# AKS.net
KiCad netlist of a schematic drawn in EAGLE
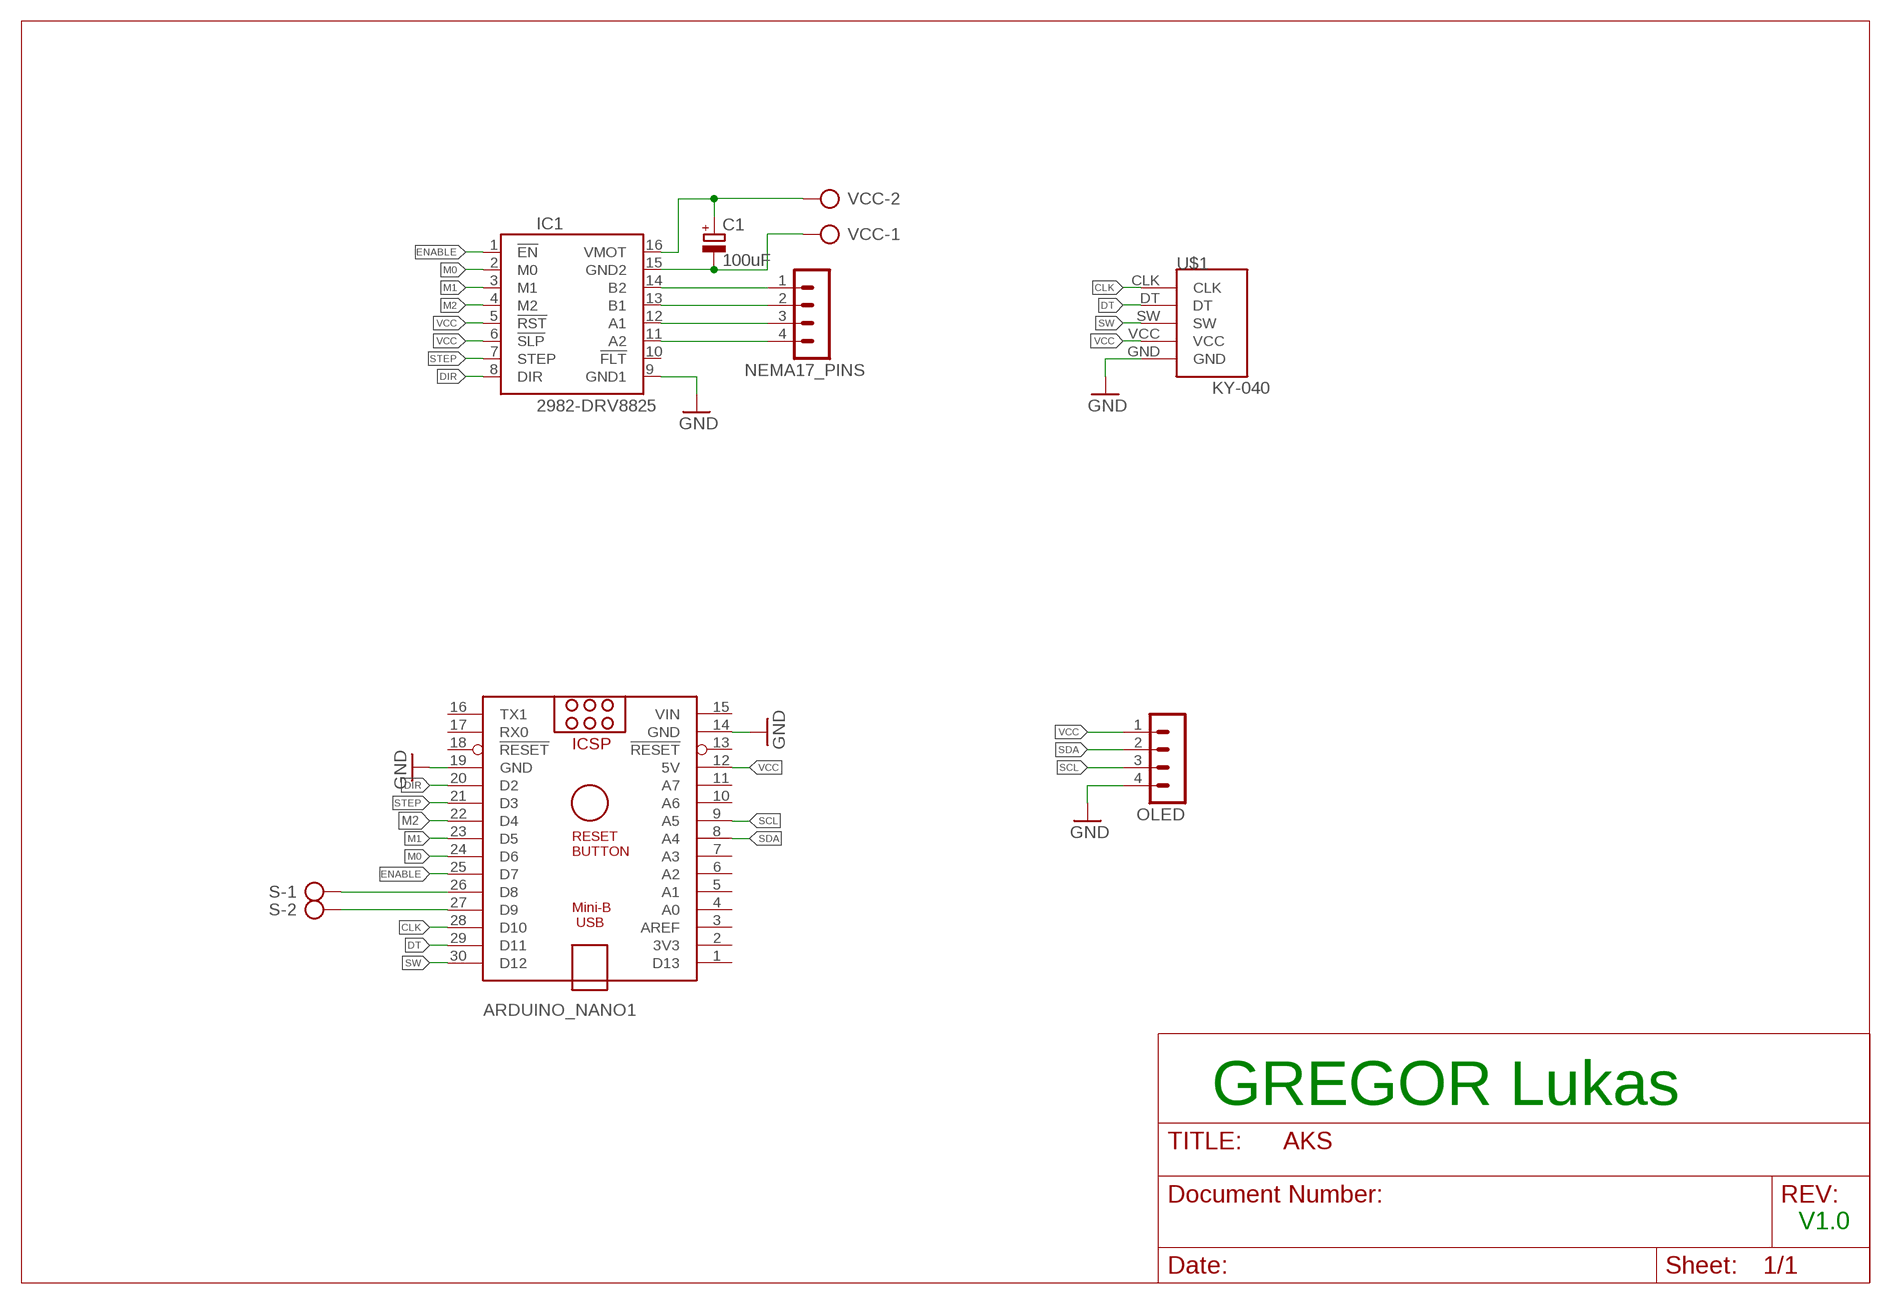
[diagram p0: schematic, sheet 1]

(export (version "E")
  (design (tool "Eeschema 10.0.6"))
  (components
    (comp (ref "ARDUINO_NANO1")
      (value "ARDUINO_NANO")
      (footprint "eagle-import:ARDUINO_NANO")
      (libsource (lib "eagle-import") (part "ARDUINO_NANO"))
    )
    (comp (ref "C1")
      (value "100uF")
      (footprint "eagle-import:E5-10,5")
      (libsource (lib "eagle-import") (part "CPOL-EUE5-10.5"))
    )
    (comp (ref "IC1")
      (value "2982-DRV8825")
      (footprint "eagle-import:DRV8825")
      (libsource (lib "eagle-import") (part "2982-DRV8825"))
    )
    (comp (ref "NEMA17_PINS")
      (value "MA04-1")
      (footprint "eagle-import:MA04-1")
      (libsource (lib "eagle-import") (part "MA04-1"))
    )
    (comp (ref "OLED")
      (value "MA04-1")
      (footprint "eagle-import:MA04-1")
      (libsource (lib "eagle-import") (part "MA04-1"))
    )
    (comp (ref "S")
      (value "AK500/2")
      (footprint "eagle-import:AK500_2")
      (libsource (lib "eagle-import") (part "AK500/2"))
    )
    (comp (ref "U$1")
      (value "KY-040")
      (footprint "eagle-import:KY-040-PORT")
      (fields (field (name "MF") "Joy-IT"))
      (libsource (lib "eagle-import") (part "KY-040"))
    )
    (comp (ref "VCC")
      (value "AK500/2")
      (footprint "eagle-import:AK500_2")
      (libsource (lib "eagle-import") (part "AK500/2"))
    )
  )
  (nets
    (net (code "1") (name "/VIN") (class "Default")
      (node (ref "ARDUINO_NANO1") (pin "15") (pinfunction "VIN_15") (pintype "power_in"))
    )
    (net (code "2") (name "CLK") (class "Default")
      (node (ref "ARDUINO_NANO1") (pin "28") (pinfunction "D10_28") (pintype "bidirectional"))
      (node (ref "U$1") (pin "CLK") (pinfunction "CLK_CLK") (pintype "output"))
    )
    (net (code "3") (name "DIR") (class "Default")
      (node (ref "ARDUINO_NANO1") (pin "20") (pinfunction "D2_20") (pintype "bidirectional"))
      (node (ref "IC1") (pin "8") (pinfunction "DIR_8") (pintype "input"))
    )
    (net (code "4") (name "DT") (class "Default")
      (node (ref "ARDUINO_NANO1") (pin "29") (pinfunction "D11_29") (pintype "bidirectional"))
      (node (ref "U$1") (pin "DT") (pinfunction "DT_DT") (pintype "output"))
    )
    (net (code "5") (name "ENABLE") (class "Default")
      (node (ref "ARDUINO_NANO1") (pin "25") (pinfunction "D7_25") (pintype "bidirectional"))
      (node (ref "IC1") (pin "1") (pinfunction "~{EN}_1") (pintype "passive"))
    )
    (net (code "6") (name "GND") (class "Default")
      (node (ref "ARDUINO_NANO1") (pin "14") (pinfunction "GND_14") (pintype "power_in"))
      (node (ref "ARDUINO_NANO1") (pin "19") (pinfunction "GND_19") (pintype "power_in"))
      (node (ref "IC1") (pin "9") (pinfunction "GND1_9") (pintype "power_in"))
      (node (ref "OLED") (pin "4") (pinfunction "4_4") (pintype "passive"))
      (node (ref "U$1") (pin "GND") (pinfunction "GND_GND") (pintype "power_in"))
    )
    (net (code "7") (name "M0") (class "Default")
      (node (ref "ARDUINO_NANO1") (pin "24") (pinfunction "D6_24") (pintype "bidirectional"))
      (node (ref "IC1") (pin "2") (pinfunction "M0_2") (pintype "passive"))
    )
    (net (code "8") (name "M1") (class "Default")
      (node (ref "ARDUINO_NANO1") (pin "23") (pinfunction "D5_23") (pintype "bidirectional"))
      (node (ref "IC1") (pin "3") (pinfunction "M1_3") (pintype "passive"))
    )
    (net (code "9") (name "M2") (class "Default")
      (node (ref "ARDUINO_NANO1") (pin "22") (pinfunction "D4_22") (pintype "bidirectional"))
      (node (ref "IC1") (pin "4") (pinfunction "M2_4") (pintype "passive"))
    )
    (net (code "10") (name "Net-(ARDUINO_NANO1-D8)") (class "Default")
      (node (ref "ARDUINO_NANO1") (pin "26") (pinfunction "D8_26") (pintype "bidirectional"))
      (node (ref "S") (pin "1") (pinfunction "KL_1") (pintype "passive"))
    )
    (net (code "11") (name "Net-(ARDUINO_NANO1-D9)") (class "Default")
      (node (ref "ARDUINO_NANO1") (pin "27") (pinfunction "D9_27") (pintype "bidirectional"))
      (node (ref "S") (pin "2") (pinfunction "KL_2") (pintype "passive"))
    )
    (net (code "12") (name "Net-(IC1-A1)") (class "Default")
      (node (ref "IC1") (pin "12") (pinfunction "A1_12") (pintype "output"))
      (node (ref "NEMA17_PINS") (pin "3") (pinfunction "3_3") (pintype "passive"))
    )
    (net (code "13") (name "Net-(IC1-A2)") (class "Default")
      (node (ref "IC1") (pin "11") (pinfunction "A2_11") (pintype "output"))
      (node (ref "NEMA17_PINS") (pin "4") (pinfunction "4_4") (pintype "passive"))
    )
    (net (code "14") (name "Net-(IC1-B1)") (class "Default")
      (node (ref "IC1") (pin "13") (pinfunction "B1_13") (pintype "output"))
      (node (ref "NEMA17_PINS") (pin "2") (pinfunction "2_2") (pintype "passive"))
    )
    (net (code "15") (name "Net-(IC1-B2)") (class "Default")
      (node (ref "IC1") (pin "14") (pinfunction "B2_14") (pintype "output"))
      (node (ref "NEMA17_PINS") (pin "1") (pinfunction "1_1") (pintype "passive"))
    )
    (net (code "16") (name "Net-(IC1-GND2)") (class "Default")
      (node (ref "C1") (pin "-") (pinfunction "-_-") (pintype "passive"))
      (node (ref "IC1") (pin "15") (pinfunction "GND2_15") (pintype "power_in"))
      (node (ref "VCC") (pin "1") (pinfunction "KL_1") (pintype "passive"))
    )
    (net (code "17") (name "Net-(IC1-VMOT)") (class "Default")
      (node (ref "C1") (pin "+") (pinfunction "+_+") (pintype "passive"))
      (node (ref "IC1") (pin "16") (pinfunction "VMOT_16") (pintype "power_in"))
      (node (ref "VCC") (pin "2") (pinfunction "KL_2") (pintype "passive"))
    )
    (net (code "18") (name "SCL") (class "Default")
      (node (ref "ARDUINO_NANO1") (pin "9") (pinfunction "A5_9") (pintype "bidirectional"))
      (node (ref "OLED") (pin "3") (pinfunction "3_3") (pintype "passive"))
    )
    (net (code "19") (name "SDA") (class "Default")
      (node (ref "ARDUINO_NANO1") (pin "8") (pinfunction "A4_8") (pintype "bidirectional"))
      (node (ref "OLED") (pin "2") (pinfunction "2_2") (pintype "passive"))
    )
    (net (code "20") (name "STEP") (class "Default")
      (node (ref "ARDUINO_NANO1") (pin "21") (pinfunction "D3_21") (pintype "bidirectional"))
      (node (ref "IC1") (pin "7") (pinfunction "STEP_7") (pintype "input"))
    )
    (net (code "21") (name "SW") (class "Default")
      (node (ref "ARDUINO_NANO1") (pin "30") (pinfunction "D12_30") (pintype "bidirectional"))
      (node (ref "U$1") (pin "SW") (pinfunction "SW_SW") (pintype "output"))
    )
    (net (code "22") (name "VCC") (class "Default")
      (node (ref "ARDUINO_NANO1") (pin "12") (pinfunction "5V_12") (pintype "power_in"))
      (node (ref "IC1") (pin "5") (pinfunction "~{RST}_5") (pintype "input"))
      (node (ref "IC1") (pin "6") (pinfunction "~{SLP}_6") (pintype "input"))
      (node (ref "OLED") (pin "1") (pinfunction "1_1") (pintype "passive"))
      (node (ref "U$1") (pin "VCC") (pinfunction "VCC_VCC") (pintype "power_in"))
    )
    (net (code "23") (name "unconnected-(ARDUINO_NANO1-3V3-Pad2)") (class "Default")
      (node (ref "ARDUINO_NANO1") (pin "2") (pinfunction "3V3_2") (pintype "output"))
    )
    (net (code "24") (name "unconnected-(ARDUINO_NANO1-A0-Pad4)") (class "Default")
      (node (ref "ARDUINO_NANO1") (pin "4") (pinfunction "A0_4") (pintype "bidirectional"))
    )
    (net (code "25") (name "unconnected-(ARDUINO_NANO1-A1-Pad5)") (class "Default")
      (node (ref "ARDUINO_NANO1") (pin "5") (pinfunction "A1_5") (pintype "bidirectional"))
    )
    (net (code "26") (name "unconnected-(ARDUINO_NANO1-A2-Pad6)") (class "Default")
      (node (ref "ARDUINO_NANO1") (pin "6") (pinfunction "A2_6") (pintype "bidirectional"))
    )
    (net (code "27") (name "unconnected-(ARDUINO_NANO1-A3-Pad7)") (class "Default")
      (node (ref "ARDUINO_NANO1") (pin "7") (pinfunction "A3_7") (pintype "bidirectional"))
    )
    (net (code "28") (name "unconnected-(ARDUINO_NANO1-A6-Pad10)") (class "Default")
      (node (ref "ARDUINO_NANO1") (pin "10") (pinfunction "A6_10") (pintype "bidirectional"))
    )
    (net (code "29") (name "unconnected-(ARDUINO_NANO1-A7-Pad11)") (class "Default")
      (node (ref "ARDUINO_NANO1") (pin "11") (pinfunction "A7_11") (pintype "bidirectional"))
    )
    (net (code "30") (name "unconnected-(ARDUINO_NANO1-AREF-Pad3)") (class "Default")
      (node (ref "ARDUINO_NANO1") (pin "3") (pinfunction "AREF_3") (pintype "input"))
    )
    (net (code "31") (name "unconnected-(ARDUINO_NANO1-D13-Pad1)") (class "Default")
      (node (ref "ARDUINO_NANO1") (pin "1") (pinfunction "D13_1") (pintype "bidirectional"))
    )
    (net (code "32") (name "unconnected-(ARDUINO_NANO1-RX0-Pad17)") (class "Default")
      (node (ref "ARDUINO_NANO1") (pin "17") (pinfunction "RX0_17") (pintype "bidirectional"))
    )
    (net (code "33") (name "unconnected-(ARDUINO_NANO1-TX1-Pad16)") (class "Default")
      (node (ref "ARDUINO_NANO1") (pin "16") (pinfunction "TX1_16") (pintype "bidirectional"))
    )
    (net (code "34") (name "unconnected-(ARDUINO_NANO1-~{RESET}-Pad13)") (class "Default")
      (node (ref "ARDUINO_NANO1") (pin "13") (pinfunction "~{RESET}_13") (pintype "input"))
    )
    (net (code "35") (name "unconnected-(ARDUINO_NANO1-~{RESET}-Pad18)") (class "Default")
      (node (ref "ARDUINO_NANO1") (pin "18") (pinfunction "~{RESET}_18") (pintype "input"))
    )
    (net (code "36") (name "unconnected-(IC1-~{FLT}-Pad10)") (class "Default")
      (node (ref "IC1") (pin "10") (pinfunction "~{FLT}_10") (pintype "open_collector"))
    )
  )
)
